# USB-LPC-Programmer_V3_5.net
KiCad netlist of a schematic drawn in EAGLE
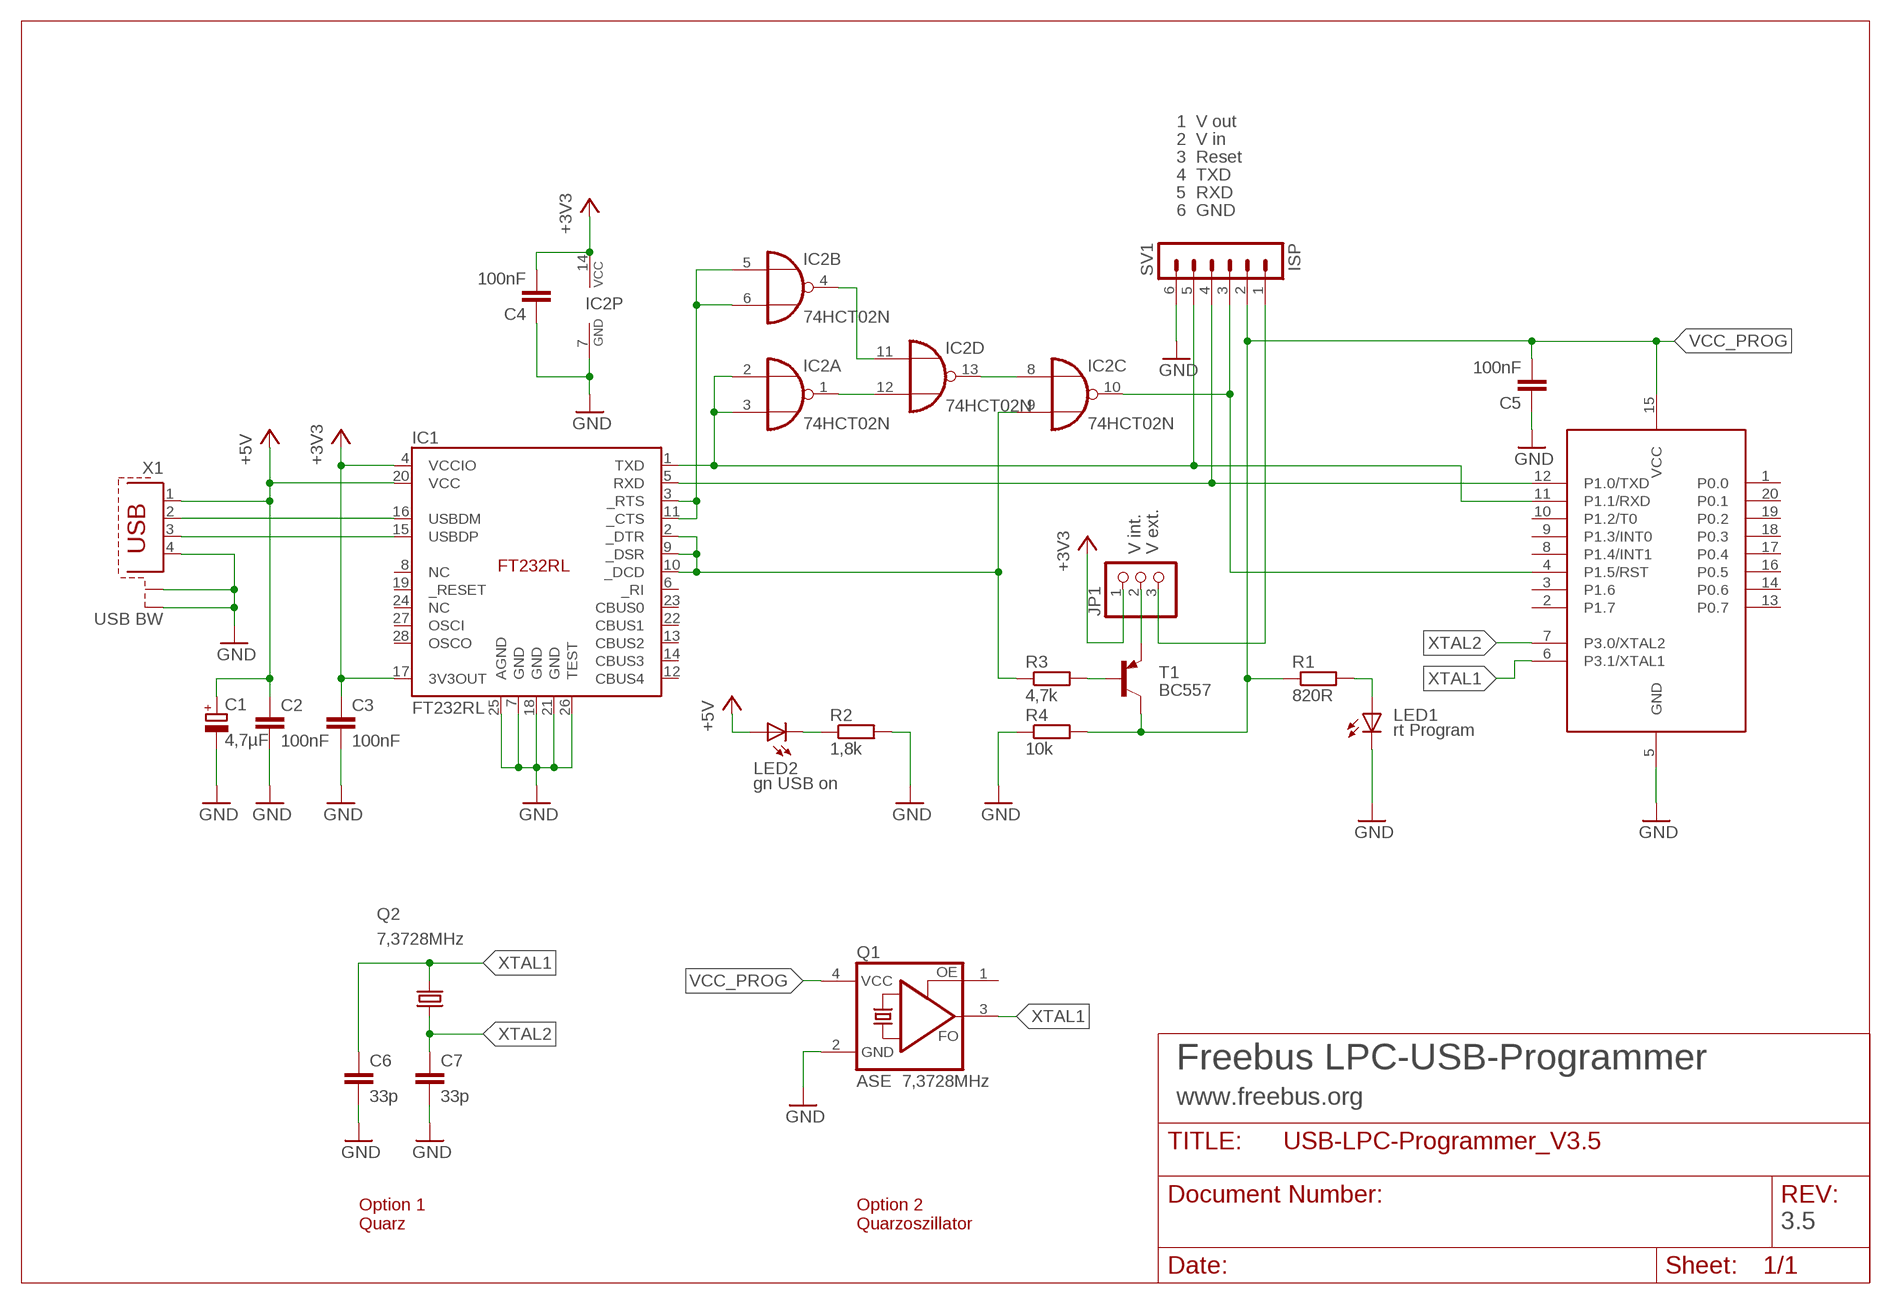
[diagram p0: schematic, sheet 1]

(export (version "E")
  (design (tool "Eeschema 10.0.6"))
  (components
    (comp (ref "89LPC922")
      (value "LPC-Sockel")
      (footprint "eagle-import:DIL20")
      (libsource (lib "eagle-import") (part "89LPC922"))
    )
    (comp (ref "C1")
      (value "4,7µF")
      (footprint "eagle-import:E2,5-6")
      (libsource (lib "eagle-import") (part "CPOL-EUE2.5-6"))
    )
    (comp (ref "C2")
      (value "100nF")
      (footprint "eagle-import:C050-024X044")
      (libsource (lib "eagle-import") (part "C-EU050-024X044"))
    )
    (comp (ref "C3")
      (value "100nF")
      (footprint "eagle-import:C050-024X044")
      (libsource (lib "eagle-import") (part "C-EU050-024X044"))
    )
    (comp (ref "C4")
      (value "100nF")
      (footprint "eagle-import:C050-024X044")
      (libsource (lib "eagle-import") (part "C-EU050-024X044"))
    )
    (comp (ref "C5")
      (value "100nF")
      (footprint "eagle-import:C050-024X044")
      (libsource (lib "eagle-import") (part "C-EU050-024X044"))
    )
    (comp (ref "C6")
      (value "33p")
      (footprint "eagle-import:C025-024X044")
      (libsource (lib "eagle-import") (part "C-EU025-024X044"))
    )
    (comp (ref "C7")
      (value "33p")
      (footprint "eagle-import:C025-024X044")
      (libsource (lib "eagle-import") (part "C-EU025-024X044"))
    )
    (comp (ref "IC1")
      (value "FT232RL")
      (footprint "eagle-import:SSOP-28")
      (libsource (lib "eagle-import") (part "FT232RL"))
    )
    (comp (ref "IC2")
      (value "74HCT02N")
      (footprint "eagle-import:DIL14")
      (libsource (lib "eagle-import") (part "7402NHCT"))
    )
    (comp (ref "JP1")
      (value "PINHD-1X3")
      (footprint "eagle-import:1X03")
      (libsource (lib "eagle-import") (part "PINHD-1X3"))
    )
    (comp (ref "LED1")
      (value "rt Program")
      (footprint "eagle-import:LED3MM")
      (libsource (lib "eagle-import") (part "LED3MM"))
    )
    (comp (ref "LED2")
      (value "gn USB on")
      (footprint "eagle-import:LED3MM")
      (libsource (lib "eagle-import") (part "LED3MM"))
    )
    (comp (ref "Q1")
      (value "ASE 7,3728MHz")
      (footprint "eagle-import:ASF")
      (libsource (lib "eagle-import") (part "ASF1"))
    )
    (comp (ref "Q2")
      (value "7,3728MHz")
      (footprint "eagle-import:HC49_S")
      (libsource (lib "eagle-import") (part "CRYSTALHC49S"))
    )
    (comp (ref "R1")
      (value "820R")
      (footprint "eagle-import:0207_7")
      (libsource (lib "eagle-import") (part "R-EU_0207/7"))
    )
    (comp (ref "R2")
      (value "1,8k")
      (footprint "eagle-import:0207_7")
      (libsource (lib "eagle-import") (part "R-EU_0207/7"))
    )
    (comp (ref "R3")
      (value "4,7k")
      (footprint "eagle-import:0204_7")
      (libsource (lib "eagle-import") (part "R-EU_0204/7"))
    )
    (comp (ref "R4")
      (value "10k")
      (footprint "eagle-import:0207_7")
      (libsource (lib "eagle-import") (part "R-EU_0207/7"))
    )
    (comp (ref "SV1")
      (value "ISP")
      (footprint "eagle-import:MA06-1")
      (libsource (lib "eagle-import") (part "MA06-1"))
    )
    (comp (ref "T1")
      (value "BC557")
      (footprint "eagle-import:TO92")
      (libsource (lib "eagle-import") (part "BC557"))
    )
    (comp (ref "X1")
      (value "USB BW")
      (footprint "eagle-import:PN61729-S")
      (libsource (lib "eagle-import") (part "PN61729-S"))
    )
  )
  (nets
    (net (code "1") (name "+3V3") (class "Default")
      (node (ref "C3") (pin "1") (pinfunction "1_1") (pintype "passive"))
      (node (ref "C4") (pin "2") (pinfunction "2_2") (pintype "passive"))
      (node (ref "IC1") (pin "17") (pinfunction "3V3OUT_17") (pintype "output"))
      (node (ref "IC1") (pin "4") (pinfunction "VCCIO_4") (pintype "power_in"))
      (node (ref "IC2") (pin "14") (pinfunction "VCC_14") (pintype "power_in"))
      (node (ref "JP1") (pin "1") (pinfunction "1_1") (pintype "passive"))
    )
    (net (code "2") (name "+5V") (class "Default")
      (node (ref "C1") (pin "+") (pinfunction "+_+") (pintype "passive"))
      (node (ref "C2") (pin "1") (pinfunction "1_1") (pintype "passive"))
      (node (ref "IC1") (pin "20") (pinfunction "VCC_20") (pintype "power_in"))
      (node (ref "LED2") (pin "A") (pinfunction "A_A") (pintype "passive"))
      (node (ref "X1") (pin "1") (pinfunction "1_1") (pintype "passive"))
    )
    (net (code "3") (name "GND") (class "Default")
      (node (ref "89LPC922") (pin "5") (pinfunction "GND_5") (pintype "bidirectional"))
      (node (ref "C1") (pin "-") (pinfunction "-_-") (pintype "passive"))
      (node (ref "C2") (pin "2") (pinfunction "2_2") (pintype "passive"))
      (node (ref "C3") (pin "2") (pinfunction "2_2") (pintype "passive"))
      (node (ref "C4") (pin "1") (pinfunction "1_1") (pintype "passive"))
      (node (ref "C5") (pin "1") (pinfunction "1_1") (pintype "passive"))
      (node (ref "C6") (pin "2") (pinfunction "2_2") (pintype "passive"))
      (node (ref "C7") (pin "2") (pinfunction "2_2") (pintype "passive"))
      (node (ref "IC1") (pin "18") (pinfunction "GND_18") (pintype "power_in"))
      (node (ref "IC1") (pin "21") (pinfunction "GND_21") (pintype "power_in"))
      (node (ref "IC1") (pin "25") (pinfunction "AGND_25") (pintype "power_in"))
      (node (ref "IC1") (pin "26") (pinfunction "TEST_26") (pintype "bidirectional"))
      (node (ref "IC1") (pin "7") (pinfunction "GND_7") (pintype "power_in"))
      (node (ref "IC2") (pin "7") (pinfunction "GND_7") (pintype "power_in"))
      (node (ref "LED1") (pin "K") (pinfunction "C_K") (pintype "passive"))
      (node (ref "Q1") (pin "2") (pinfunction "GND_2") (pintype "power_in"))
      (node (ref "R2") (pin "2") (pinfunction "2_2") (pintype "passive"))
      (node (ref "R4") (pin "1") (pinfunction "1_1") (pintype "passive"))
      (node (ref "SV1") (pin "6") (pinfunction "6_6") (pintype "passive"))
      (node (ref "X1") (pin "4") (pinfunction "4_4") (pintype "passive"))
      (node (ref "X1") (pin "S1") (pinfunction "S1_S1") (pintype "passive"))
      (node (ref "X1") (pin "S2") (pinfunction "S2_S2") (pintype "passive"))
    )
    (net (code "4") (name "Net-(89LPC922-P1.0{slash}TXD)") (class "Default")
      (node (ref "89LPC922") (pin "12") (pinfunction "P1.0/TXD_12") (pintype "bidirectional"))
      (node (ref "IC1") (pin "5") (pinfunction "RXD_5") (pintype "input"))
      (node (ref "SV1") (pin "4") (pinfunction "4_4") (pintype "passive"))
    )
    (net (code "5") (name "Net-(89LPC922-P1.1{slash}RXD)") (class "Default")
      (node (ref "89LPC922") (pin "11") (pinfunction "P1.1/RXD_11") (pintype "bidirectional"))
      (node (ref "IC1") (pin "1") (pinfunction "TXD_1") (pintype "output"))
      (node (ref "IC2") (pin "2") (pinfunction "I0_2") (pintype "input"))
      (node (ref "IC2") (pin "3") (pinfunction "I1_3") (pintype "input"))
      (node (ref "SV1") (pin "5") (pinfunction "5_5") (pintype "passive"))
    )
    (net (code "6") (name "Net-(89LPC922-P1.5{slash}RST)") (class "Default")
      (node (ref "89LPC922") (pin "4") (pinfunction "P1.5/RST_4") (pintype "bidirectional"))
      (node (ref "IC2") (pin "10") (pinfunction "O_10") (pintype "output"))
      (node (ref "SV1") (pin "3") (pinfunction "3_3") (pintype "passive"))
    )
    (net (code "7") (name "Net-(IC1-USBDM)") (class "Default")
      (node (ref "IC1") (pin "16") (pinfunction "USBDM_16") (pintype "bidirectional"))
      (node (ref "X1") (pin "2") (pinfunction "2_2") (pintype "passive"))
    )
    (net (code "8") (name "Net-(IC1-USBDP)") (class "Default")
      (node (ref "IC1") (pin "15") (pinfunction "USBDP_15") (pintype "bidirectional"))
      (node (ref "X1") (pin "3") (pinfunction "3_3") (pintype "passive"))
    )
    (net (code "9") (name "Net-(IC1-_CTS)") (class "Default")
      (node (ref "IC1") (pin "11") (pinfunction "_CTS_11") (pintype "input"))
      (node (ref "IC1") (pin "3") (pinfunction "_RTS_3") (pintype "output"))
      (node (ref "IC2") (pin "5") (pinfunction "I0_5") (pintype "input"))
      (node (ref "IC2") (pin "6") (pinfunction "I1_6") (pintype "input"))
    )
    (net (code "10") (name "Net-(IC1-_DCD)") (class "Default")
      (node (ref "IC1") (pin "10") (pinfunction "_DCD_10") (pintype "input"))
      (node (ref "IC1") (pin "2") (pinfunction "_DTR_2") (pintype "input"))
      (node (ref "IC1") (pin "9") (pinfunction "_DSR_9") (pintype "input"))
      (node (ref "IC2") (pin "9") (pinfunction "I1_9") (pintype "input"))
      (node (ref "R3") (pin "1") (pinfunction "1_1") (pintype "passive"))
    )
    (net (code "11") (name "Net-(IC2A-O)") (class "Default")
      (node (ref "IC2") (pin "1") (pinfunction "O_1") (pintype "output"))
      (node (ref "IC2") (pin "12") (pinfunction "I1_12") (pintype "input"))
    )
    (net (code "12") (name "Net-(IC2B-O)") (class "Default")
      (node (ref "IC2") (pin "11") (pinfunction "I0_11") (pintype "input"))
      (node (ref "IC2") (pin "4") (pinfunction "O_4") (pintype "output"))
    )
    (net (code "13") (name "Net-(IC2C-I0)") (class "Default")
      (node (ref "IC2") (pin "13") (pinfunction "O_13") (pintype "output"))
      (node (ref "IC2") (pin "8") (pinfunction "I0_8") (pintype "input"))
    )
    (net (code "14") (name "Net-(JP1-Pad3)") (class "Default")
      (node (ref "JP1") (pin "3") (pinfunction "3_3") (pintype "passive"))
      (node (ref "SV1") (pin "1") (pinfunction "1_1") (pintype "passive"))
    )
    (net (code "15") (name "Net-(LED1-PadA)") (class "Default")
      (node (ref "LED1") (pin "A") (pinfunction "A_A") (pintype "passive"))
      (node (ref "R1") (pin "2") (pinfunction "2_2") (pintype "passive"))
    )
    (net (code "16") (name "Net-(LED2-C)") (class "Default")
      (node (ref "LED2") (pin "K") (pinfunction "C_K") (pintype "passive"))
      (node (ref "R2") (pin "1") (pinfunction "1_1") (pintype "passive"))
    )
    (net (code "17") (name "Net-(T1-B)") (class "Default")
      (node (ref "R3") (pin "2") (pinfunction "2_2") (pintype "passive"))
      (node (ref "T1") (pin "2") (pinfunction "B_2") (pintype "passive"))
    )
    (net (code "18") (name "Net-(T1-E)") (class "Default")
      (node (ref "JP1") (pin "2") (pinfunction "2_2") (pintype "passive"))
      (node (ref "T1") (pin "1") (pinfunction "E_1") (pintype "passive"))
    )
    (net (code "19") (name "VCC_PROG") (class "Default")
      (node (ref "89LPC922") (pin "15") (pinfunction "VCC_15") (pintype "bidirectional"))
      (node (ref "C5") (pin "2") (pinfunction "2_2") (pintype "passive"))
      (node (ref "Q1") (pin "4") (pinfunction "VCC_4") (pintype "power_in"))
      (node (ref "R1") (pin "1") (pinfunction "1_1") (pintype "passive"))
      (node (ref "R4") (pin "2") (pinfunction "2_2") (pintype "passive"))
      (node (ref "SV1") (pin "2") (pinfunction "2_2") (pintype "passive"))
      (node (ref "T1") (pin "3") (pinfunction "C_3") (pintype "passive"))
    )
    (net (code "20") (name "XTAL1") (class "Default")
      (node (ref "89LPC922") (pin "6") (pinfunction "P3.1/XTAL1_6") (pintype "bidirectional"))
      (node (ref "C6") (pin "1") (pinfunction "1_1") (pintype "passive"))
      (node (ref "Q1") (pin "3") (pinfunction "FO_3") (pintype "output"))
      (node (ref "Q2") (pin "2") (pinfunction "2_2") (pintype "passive"))
    )
    (net (code "21") (name "XTAL2") (class "Default")
      (node (ref "89LPC922") (pin "7") (pinfunction "P3.0/XTAL2_7") (pintype "bidirectional"))
      (node (ref "C7") (pin "1") (pinfunction "1_1") (pintype "passive"))
      (node (ref "Q2") (pin "1") (pinfunction "1_1") (pintype "passive"))
    )
    (net (code "22") (name "unconnected-(89LPC922-P0.0-Pad1)") (class "Default")
      (node (ref "89LPC922") (pin "1") (pinfunction "P0.0_1") (pintype "bidirectional"))
    )
    (net (code "23") (name "unconnected-(89LPC922-P0.1-Pad20)") (class "Default")
      (node (ref "89LPC922") (pin "20") (pinfunction "P0.1_20") (pintype "bidirectional"))
    )
    (net (code "24") (name "unconnected-(89LPC922-P0.2-Pad19)") (class "Default")
      (node (ref "89LPC922") (pin "19") (pinfunction "P0.2_19") (pintype "bidirectional"))
    )
    (net (code "25") (name "unconnected-(89LPC922-P0.3-Pad18)") (class "Default")
      (node (ref "89LPC922") (pin "18") (pinfunction "P0.3_18") (pintype "bidirectional"))
    )
    (net (code "26") (name "unconnected-(89LPC922-P0.4-Pad17)") (class "Default")
      (node (ref "89LPC922") (pin "17") (pinfunction "P0.4_17") (pintype "bidirectional"))
    )
    (net (code "27") (name "unconnected-(89LPC922-P0.5-Pad16)") (class "Default")
      (node (ref "89LPC922") (pin "16") (pinfunction "P0.5_16") (pintype "bidirectional"))
    )
    (net (code "28") (name "unconnected-(89LPC922-P0.6-Pad14)") (class "Default")
      (node (ref "89LPC922") (pin "14") (pinfunction "P0.6_14") (pintype "bidirectional"))
    )
    (net (code "29") (name "unconnected-(89LPC922-P0.7-Pad13)") (class "Default")
      (node (ref "89LPC922") (pin "13") (pinfunction "P0.7_13") (pintype "bidirectional"))
    )
    (net (code "30") (name "unconnected-(89LPC922-P1.2{slash}T0-Pad10)") (class "Default")
      (node (ref "89LPC922") (pin "10") (pinfunction "P1.2/T0_10") (pintype "bidirectional"))
    )
    (net (code "31") (name "unconnected-(89LPC922-P1.3{slash}INT0-Pad9)") (class "Default")
      (node (ref "89LPC922") (pin "9") (pinfunction "P1.3/INT0_9") (pintype "bidirectional"))
    )
    (net (code "32") (name "unconnected-(89LPC922-P1.4{slash}INT1-Pad8)") (class "Default")
      (node (ref "89LPC922") (pin "8") (pinfunction "P1.4/INT1_8") (pintype "bidirectional"))
    )
    (net (code "33") (name "unconnected-(89LPC922-P1.6-Pad3)") (class "Default")
      (node (ref "89LPC922") (pin "3") (pinfunction "P1.6_3") (pintype "bidirectional"))
    )
    (net (code "34") (name "unconnected-(89LPC922-P1.7-Pad2)") (class "Default")
      (node (ref "89LPC922") (pin "2") (pinfunction "P1.7_2") (pintype "bidirectional"))
    )
    (net (code "35") (name "unconnected-(IC1-CBUS0-Pad23)") (class "Default")
      (node (ref "IC1") (pin "23") (pinfunction "CBUS0_23") (pintype "bidirectional"))
    )
    (net (code "36") (name "unconnected-(IC1-CBUS1-Pad22)") (class "Default")
      (node (ref "IC1") (pin "22") (pinfunction "CBUS1_22") (pintype "bidirectional"))
    )
    (net (code "37") (name "unconnected-(IC1-CBUS2-Pad13)") (class "Default")
      (node (ref "IC1") (pin "13") (pinfunction "CBUS2_13") (pintype "bidirectional"))
    )
    (net (code "38") (name "unconnected-(IC1-CBUS3-Pad14)") (class "Default")
      (node (ref "IC1") (pin "14") (pinfunction "CBUS3_14") (pintype "bidirectional"))
    )
    (net (code "39") (name "unconnected-(IC1-CBUS4-Pad12)") (class "Default")
      (node (ref "IC1") (pin "12") (pinfunction "CBUS4_12") (pintype "bidirectional"))
    )
    (net (code "40") (name "unconnected-(IC1-NC-Pad8)") (class "Default")
      (node (ref "IC1") (pin "8") (pinfunction "NC_8") (pintype "no_connect"))
    )
    (net (code "41") (name "unconnected-(IC1-NC-Pad24)") (class "Default")
      (node (ref "IC1") (pin "24") (pinfunction "NC_24") (pintype "no_connect"))
    )
    (net (code "42") (name "unconnected-(IC1-OSCI-Pad27)") (class "Default")
      (node (ref "IC1") (pin "27") (pinfunction "OSCI_27") (pintype "input"))
    )
    (net (code "43") (name "unconnected-(IC1-OSCO-Pad28)") (class "Default")
      (node (ref "IC1") (pin "28") (pinfunction "OSCO_28") (pintype "output"))
    )
    (net (code "44") (name "unconnected-(IC1-_RESET-Pad19)") (class "Default")
      (node (ref "IC1") (pin "19") (pinfunction "_RESET_19") (pintype "input"))
    )
    (net (code "45") (name "unconnected-(IC1-_RI-Pad6)") (class "Default")
      (node (ref "IC1") (pin "6") (pinfunction "_RI_6") (pintype "input"))
    )
    (net (code "46") (name "unconnected-(Q1-OE-Pad1)") (class "Default")
      (node (ref "Q1") (pin "1") (pinfunction "OE_1") (pintype "input"))
    )
  )
)
